# feather-v2_0.net
KiCad netlist of a schematic drawn in EAGLE
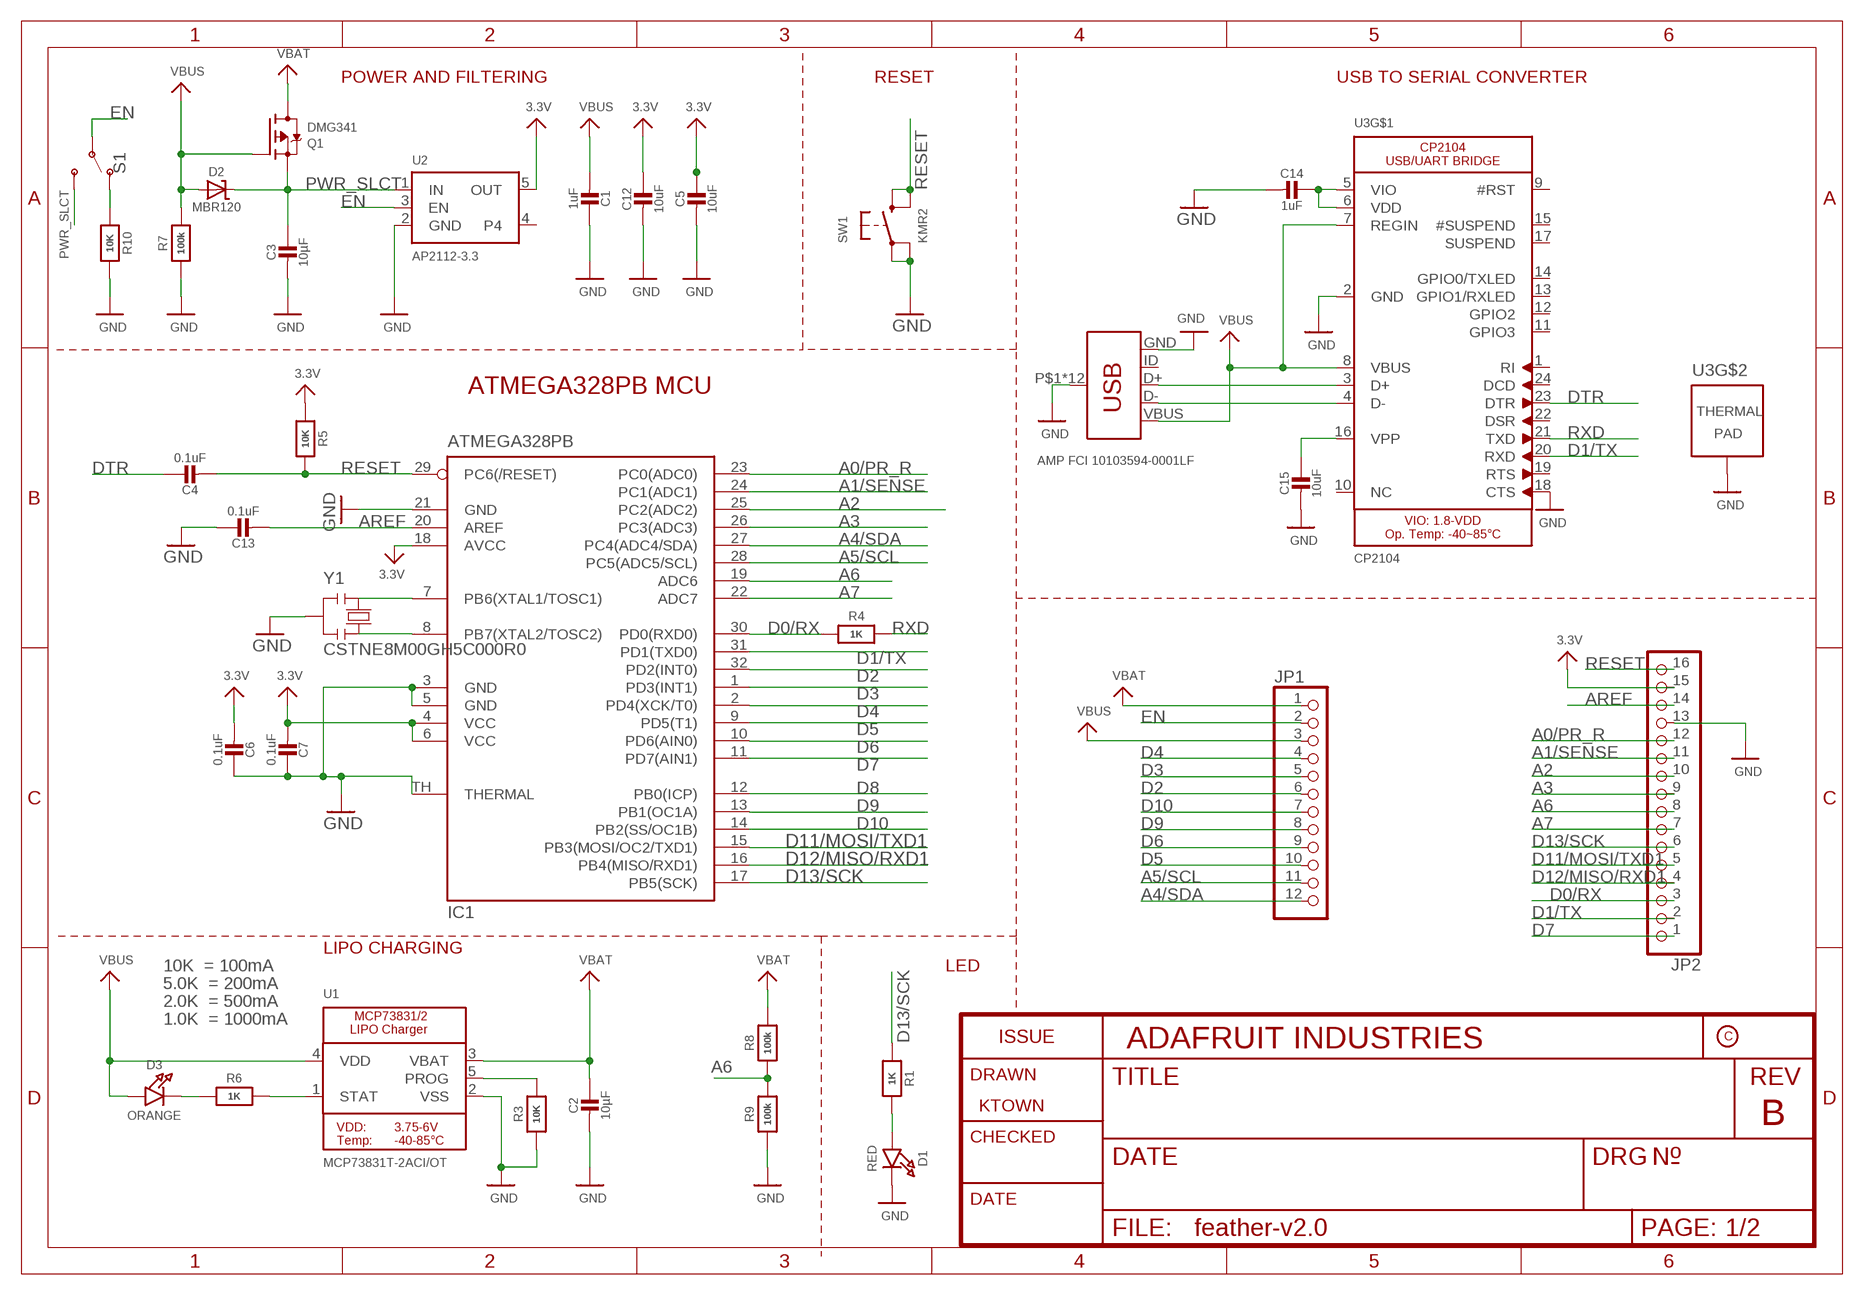
[diagram p0: schematic, sheet 1]
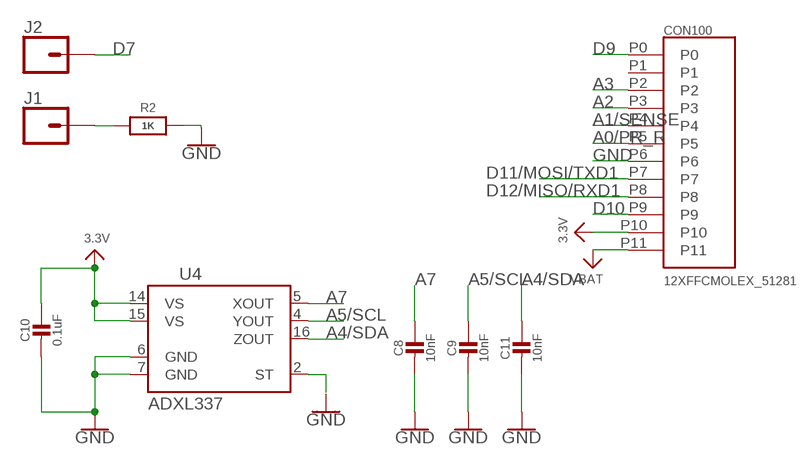
[diagram p1: schematic, sheet 2]

(export (version "E")
  (design (tool "Eeschema 10.0.6"))
  (components
    (comp (ref "C8")
      (value "10nF")
      (footprint "eagle-import:_0603MP")
      (libsource (lib "eagle-import") (part "CAP_CERAMIC_0603MP"))
    )
    (comp (ref "C9")
      (value "10nF")
      (footprint "eagle-import:_0603MP")
      (libsource (lib "eagle-import") (part "CAP_CERAMIC_0603MP"))
    )
    (comp (ref "C10")
      (value "0.1uF")
      (footprint "eagle-import:_0603MP")
      (libsource (lib "eagle-import") (part "CAP_CERAMIC_0603MP"))
    )
    (comp (ref "C11")
      (value "10nF")
      (footprint "eagle-import:_0603MP")
      (libsource (lib "eagle-import") (part "CAP_CERAMIC_0603MP"))
    )
    (comp (ref "CON100")
      (value "12XFFCMOLEX_51281")
      (footprint "eagle-import:MOLEX_51281-1294")
      (libsource (lib "eagle-import") (part "12XFFCMOLEX_51281"))
    )
    (comp (ref "J1")
      (value "CONN_01PTH_NO_SILK_YES_STOP")
      (footprint "eagle-import:1X01_NO_SILK")
      (libsource (lib "eagle-import") (part "CONN_01PTH_NO_SILK_YES_STOP"))
    )
    (comp (ref "J2")
      (value "CONN_01PTH_NO_SILK_YES_STOP")
      (footprint "eagle-import:1X01_NO_SILK")
      (libsource (lib "eagle-import") (part "CONN_01PTH_NO_SILK_YES_STOP"))
    )
    (comp (ref "R2")
      (value "1K")
      (footprint "eagle-import:_0603MP")
      (libsource (lib "eagle-import") (part "RESISTOR_0603MP"))
    )
    (comp (ref "U4")
      (value "ADXL337")
      (footprint "eagle-import:LFCSP_LQ-16")
      (libsource (lib "eagle-import") (part "ADXL337"))
    )
    (comp (ref "C1")
      (value "1uF")
      (footprint "eagle-import:_0603MP")
      (libsource (lib "eagle-import") (part "CAP_CERAMIC_0603MP"))
    )
    (comp (ref "C2")
      (value "10µF")
      (footprint "eagle-import:_0603MP")
      (libsource (lib "eagle-import") (part "CAP_CERAMIC_0603MP"))
    )
    (comp (ref "C3")
      (value "10µF")
      (footprint "eagle-import:_0603MP")
      (libsource (lib "eagle-import") (part "CAP_CERAMIC_0603MP"))
    )
    (comp (ref "C4")
      (value "0.1uF")
      (footprint "eagle-import:_0603MP")
      (libsource (lib "eagle-import") (part "CAP_CERAMIC_0603MP"))
    )
    (comp (ref "C5")
      (value "10uF")
      (footprint "eagle-import:_0603MP")
      (libsource (lib "eagle-import") (part "CAP_CERAMIC_0603MP"))
    )
    (comp (ref "C6")
      (value "0.1uF")
      (footprint "eagle-import:_0603MP")
      (libsource (lib "eagle-import") (part "CAP_CERAMIC_0603MP"))
    )
    (comp (ref "C7")
      (value "0.1uF")
      (footprint "eagle-import:_0603MP")
      (libsource (lib "eagle-import") (part "CAP_CERAMIC_0603MP"))
    )
    (comp (ref "C12")
      (value "10uF")
      (footprint "eagle-import:_0603MP")
      (libsource (lib "eagle-import") (part "CAP_CERAMIC_0603MP"))
    )
    (comp (ref "C13")
      (value "0.1uF")
      (footprint "eagle-import:_0603MP")
      (libsource (lib "eagle-import") (part "CAP_CERAMIC_0603MP"))
    )
    (comp (ref "C14")
      (value "1uF")
      (footprint "eagle-import:_0603MP")
      (libsource (lib "eagle-import") (part "CAP_CERAMIC_0603MP"))
    )
    (comp (ref "C15")
      (value "10uF")
      (footprint "eagle-import:_0603MP")
      (libsource (lib "eagle-import") (part "CAP_CERAMIC_0603MP"))
    )
    (comp (ref "D1")
      (value "RED")
      (footprint "eagle-import:CHIPLED_0603_NOOUTLINE")
      (libsource (lib "eagle-import") (part "LED0603_NOOUTLINE"))
    )
    (comp (ref "D2")
      (value "MBR120")
      (footprint "eagle-import:SOD-323")
      (libsource (lib "eagle-import") (part "DIODE-SCHOTTKYSOD-323"))
    )
    (comp (ref "D3")
      (value "ORANGE")
      (footprint "eagle-import:CHIPLED_0603_NOOUTLINE")
      (libsource (lib "eagle-import") (part "LED0603_NOOUTLINE"))
    )
    (comp (ref "IC1")
      (value "ATMEGA328PB")
      (footprint "eagle-import:MLF32-TH")
      (fields (field (name "MPN") "ATMEGA88PA-MU"))
      (libsource (lib "eagle-import") (part "MEGA8-MI"))
    )
    (comp (ref "JP1")
      (value "HEADER-1X12")
      (footprint "eagle-import:1X12_ROUND")
      (libsource (lib "eagle-import") (part "HEADER-1X12"))
    )
    (comp (ref "JP2")
      (value "HEADER-1X16ROUND")
      (footprint "eagle-import:1X16_ROUND")
      (libsource (lib "eagle-import") (part "HEADER-1X16ROUND"))
    )
    (comp (ref "Q1")
      (value "DMG341")
      (footprint "eagle-import:SOT23-R")
      (libsource (lib "eagle-import") (part "MOSFET-P"))
    )
    (comp (ref "R1")
      (value "1K")
      (footprint "eagle-import:_0603MP")
      (libsource (lib "eagle-import") (part "RESISTOR_0603MP"))
    )
    (comp (ref "R3")
      (value "10K")
      (footprint "eagle-import:_0603MP")
      (libsource (lib "eagle-import") (part "RESISTOR_0603MP"))
    )
    (comp (ref "R4")
      (value "1K")
      (footprint "eagle-import:_0603MP")
      (libsource (lib "eagle-import") (part "RESISTOR_0603MP"))
    )
    (comp (ref "R5")
      (value "10K")
      (footprint "eagle-import:_0603MP")
      (libsource (lib "eagle-import") (part "RESISTOR_0603MP"))
    )
    (comp (ref "R6")
      (value "1K")
      (footprint "eagle-import:_0603MP")
      (libsource (lib "eagle-import") (part "RESISTOR_0603MP"))
    )
    (comp (ref "R7")
      (value "100k")
      (footprint "eagle-import:_0603MP")
      (libsource (lib "eagle-import") (part "RESISTOR_0603MP"))
    )
    (comp (ref "R8")
      (value "100k")
      (footprint "eagle-import:_0603MP")
      (libsource (lib "eagle-import") (part "RESISTOR_0603MP"))
    )
    (comp (ref "R9")
      (value "100k")
      (footprint "eagle-import:_0603MP")
      (libsource (lib "eagle-import") (part "RESISTOR_0603MP"))
    )
    (comp (ref "R10")
      (value "10K")
      (footprint "eagle-import:_0603MP")
      (libsource (lib "eagle-import") (part "RESISTOR_0603MP"))
    )
    (comp (ref "S1")
      (value "SWITCH-SPDT-SMD-RIGHT-ANGLE")
      (footprint "eagle-import:SWITCH_SPST_SMD_A")
      (libsource (lib "eagle-import") (part "SWITCH-SPDT-SMD-RIGHT-ANGLE"))
    )
    (comp (ref "SW1")
      (value "KMR2")
      (footprint "eagle-import:BTN_KMR2_4.6X2.8")
      (libsource (lib "eagle-import") (part "SWITCH_TACT_SMT4.6X2.8"))
    )
    (comp (ref "U1")
      (value "MCP73831T-2ACI/OT")
      (footprint "eagle-import:SOT23-5")
      (libsource (lib "eagle-import") (part "MCP73831/2"))
    )
    (comp (ref "U2")
      (value "AP2112-3.3")
      (footprint "eagle-import:SOT23-5")
      (libsource (lib "eagle-import") (part "VREG_SOT23-5"))
    )
    (comp (ref "U3")
      (value "CP2104")
      (footprint "eagle-import:QFN24_4MM_SMSC")
      (libsource (lib "eagle-import") (part "CP2104"))
    )
    (comp (ref "X1")
      (value "AMP FCI 10103594-0001LF")
      (footprint "eagle-import:USB-MICROB-PTH")
      (libsource (lib "eagle-import") (part "USB_MICRO-B_HALF_PTH"))
    )
    (comp (ref "Y1")
      (value "CSTNE8M00GH5C000R0")
      (footprint "eagle-import:RESONATOR")
      (libsource (lib "eagle-import") (part "RESONATORMU"))
    )
  )
  (nets
    (net (code "1") (name "3.3V") (class "Default")
      (node (ref "C10") (pin "1") (pinfunction "1_1") (pintype "passive"))
      (node (ref "C12") (pin "1") (pinfunction "1_1") (pintype "passive"))
      (node (ref "C5") (pin "1") (pinfunction "1_1") (pintype "passive"))
      (node (ref "C6") (pin "2") (pinfunction "2_2") (pintype "passive"))
      (node (ref "C7") (pin "2") (pinfunction "2_2") (pintype "passive"))
      (node (ref "CON100") (pin "P10") (pinfunction "P10_P10") (pintype "bidirectional"))
      (node (ref "IC1") (pin "18") (pinfunction "AVCC_18") (pintype "power_in"))
      (node (ref "IC1") (pin "4") (pinfunction "VCC_4") (pintype "power_in"))
      (node (ref "IC1") (pin "6") (pinfunction "VCC_6") (pintype "power_in"))
      (node (ref "JP2") (pin "15") (pinfunction "15_15") (pintype "passive"))
      (node (ref "R5") (pin "2") (pinfunction "2_2") (pintype "passive"))
      (node (ref "U2") (pin "5") (pinfunction "OUT_5") (pintype "power_in"))
      (node (ref "U4") (pin "14") (pinfunction "VS_14") (pintype "bidirectional"))
      (node (ref "U4") (pin "15") (pinfunction "VS_15") (pintype "bidirectional"))
    )
    (net (code "2") (name "A0{slash}PR_R") (class "Default")
      (node (ref "CON100") (pin "P5") (pinfunction "P5_P5") (pintype "bidirectional"))
      (node (ref "IC1") (pin "23") (pinfunction "PC0(ADC0)_23") (pintype "bidirectional"))
      (node (ref "JP2") (pin "12") (pinfunction "12_12") (pintype "passive"))
    )
    (net (code "3") (name "A1{slash}SENSE") (class "Default")
      (node (ref "CON100") (pin "P4") (pinfunction "P4_P4") (pintype "bidirectional"))
      (node (ref "IC1") (pin "24") (pinfunction "PC1(ADC1)_24") (pintype "bidirectional"))
      (node (ref "JP2") (pin "11") (pinfunction "11_11") (pintype "passive"))
    )
    (net (code "4") (name "A2") (class "Default")
      (node (ref "CON100") (pin "P3") (pinfunction "P3_P3") (pintype "bidirectional"))
      (node (ref "IC1") (pin "25") (pinfunction "PC2(ADC2)_25") (pintype "bidirectional"))
      (node (ref "JP2") (pin "10") (pinfunction "10_10") (pintype "passive"))
    )
    (net (code "5") (name "A3") (class "Default")
      (node (ref "CON100") (pin "P2") (pinfunction "P2_P2") (pintype "bidirectional"))
      (node (ref "IC1") (pin "26") (pinfunction "PC3(ADC3)_26") (pintype "bidirectional"))
      (node (ref "JP2") (pin "9") (pinfunction "9_9") (pintype "passive"))
    )
    (net (code "6") (name "A4{slash}SDA") (class "Default")
      (node (ref "C11") (pin "1") (pinfunction "1_1") (pintype "passive"))
      (node (ref "IC1") (pin "27") (pinfunction "PC4(ADC4/SDA)_27") (pintype "bidirectional"))
      (node (ref "JP1") (pin "12") (pinfunction "12_12") (pintype "passive"))
      (node (ref "U4") (pin "16") (pinfunction "ZOUT_16") (pintype "bidirectional"))
    )
    (net (code "7") (name "A5{slash}SCL") (class "Default")
      (node (ref "C9") (pin "1") (pinfunction "1_1") (pintype "passive"))
      (node (ref "IC1") (pin "28") (pinfunction "PC5(ADC5/SCL)_28") (pintype "bidirectional"))
      (node (ref "JP1") (pin "11") (pinfunction "11_11") (pintype "passive"))
      (node (ref "U4") (pin "4") (pinfunction "YOUT_4") (pintype "bidirectional"))
    )
    (net (code "8") (name "A6") (class "Default")
      (node (ref "IC1") (pin "19") (pinfunction "ADC6_19") (pintype "bidirectional"))
      (node (ref "JP2") (pin "8") (pinfunction "8_8") (pintype "passive"))
      (node (ref "R8") (pin "1") (pinfunction "1_1") (pintype "passive"))
      (node (ref "R9") (pin "2") (pinfunction "2_2") (pintype "passive"))
    )
    (net (code "9") (name "A7") (class "Default")
      (node (ref "C8") (pin "1") (pinfunction "1_1") (pintype "passive"))
      (node (ref "IC1") (pin "22") (pinfunction "ADC7_22") (pintype "bidirectional"))
      (node (ref "JP2") (pin "7") (pinfunction "7_7") (pintype "passive"))
      (node (ref "U4") (pin "5") (pinfunction "XOUT_5") (pintype "bidirectional"))
    )
    (net (code "10") (name "AREF") (class "Default")
      (node (ref "C13") (pin "2") (pinfunction "2_2") (pintype "passive"))
      (node (ref "IC1") (pin "20") (pinfunction "AREF_20") (pintype "passive"))
      (node (ref "JP2") (pin "14") (pinfunction "14_14") (pintype "passive"))
    )
    (net (code "11") (name "D0{slash}RX") (class "Default")
      (node (ref "IC1") (pin "30") (pinfunction "PD0(RXD0)_30") (pintype "bidirectional"))
      (node (ref "JP2") (pin "3") (pinfunction "3_3") (pintype "passive"))
      (node (ref "R4") (pin "1") (pinfunction "1_1") (pintype "passive"))
    )
    (net (code "12") (name "D1{slash}TX") (class "Default")
      (node (ref "IC1") (pin "31") (pinfunction "PD1(TXD0)_31") (pintype "bidirectional"))
      (node (ref "JP2") (pin "2") (pinfunction "2_2") (pintype "passive"))
      (node (ref "U3") (pin "20") (pinfunction "RXD_20") (pintype "input"))
    )
    (net (code "13") (name "D2") (class "Default")
      (node (ref "IC1") (pin "32") (pinfunction "PD2(INT0)_32") (pintype "bidirectional"))
      (node (ref "JP1") (pin "6") (pinfunction "6_6") (pintype "passive"))
    )
    (net (code "14") (name "D3") (class "Default")
      (node (ref "IC1") (pin "1") (pinfunction "PD3(INT1)_1") (pintype "bidirectional"))
      (node (ref "JP1") (pin "5") (pinfunction "5_5") (pintype "passive"))
    )
    (net (code "15") (name "D4") (class "Default")
      (node (ref "IC1") (pin "2") (pinfunction "PD4(XCK/T0)_2") (pintype "bidirectional"))
      (node (ref "JP1") (pin "4") (pinfunction "4_4") (pintype "passive"))
    )
    (net (code "16") (name "D5") (class "Default")
      (node (ref "IC1") (pin "9") (pinfunction "PD5(T1)_9") (pintype "bidirectional"))
      (node (ref "JP1") (pin "10") (pinfunction "10_10") (pintype "passive"))
    )
    (net (code "17") (name "D6") (class "Default")
      (node (ref "IC1") (pin "10") (pinfunction "PD6(AIN0)_10") (pintype "bidirectional"))
      (node (ref "JP1") (pin "9") (pinfunction "9_9") (pintype "passive"))
    )
    (net (code "18") (name "D7") (class "Default")
      (node (ref "IC1") (pin "11") (pinfunction "PD7(AIN1)_11") (pintype "bidirectional"))
      (node (ref "J2") (pin "1") (pinfunction "1_1") (pintype "passive"))
      (node (ref "JP2") (pin "1") (pinfunction "1_1") (pintype "passive"))
    )
    (net (code "19") (name "D8") (class "Default")
      (node (ref "IC1") (pin "12") (pinfunction "PB0(ICP)_12") (pintype "bidirectional"))
    )
    (net (code "20") (name "D9") (class "Default")
      (node (ref "CON100") (pin "P0") (pinfunction "P0_P0") (pintype "bidirectional"))
      (node (ref "IC1") (pin "13") (pinfunction "PB1(OC1A)_13") (pintype "bidirectional"))
      (node (ref "JP1") (pin "8") (pinfunction "8_8") (pintype "passive"))
    )
    (net (code "21") (name "D10") (class "Default")
      (node (ref "CON100") (pin "P9") (pinfunction "P9_P9") (pintype "bidirectional"))
      (node (ref "IC1") (pin "14") (pinfunction "PB2(SS/OC1B)_14") (pintype "bidirectional"))
      (node (ref "JP1") (pin "7") (pinfunction "7_7") (pintype "passive"))
    )
    (net (code "22") (name "D11{slash}MOSI{slash}TXD1") (class "Default")
      (node (ref "CON100") (pin "P7") (pinfunction "P7_P7") (pintype "bidirectional"))
      (node (ref "IC1") (pin "15") (pinfunction "PB3(MOSI/OC2/TXD1)_15") (pintype "bidirectional"))
      (node (ref "JP2") (pin "5") (pinfunction "5_5") (pintype "passive"))
    )
    (net (code "23") (name "D12{slash}MISO{slash}RXD1") (class "Default")
      (node (ref "CON100") (pin "P8") (pinfunction "P8_P8") (pintype "bidirectional"))
      (node (ref "IC1") (pin "16") (pinfunction "PB4(MISO/RXD1)_16") (pintype "bidirectional"))
      (node (ref "JP2") (pin "4") (pinfunction "4_4") (pintype "passive"))
    )
    (net (code "24") (name "D13{slash}SCK") (class "Default")
      (node (ref "IC1") (pin "17") (pinfunction "PB5(SCK)_17") (pintype "bidirectional"))
      (node (ref "JP2") (pin "6") (pinfunction "6_6") (pintype "passive"))
      (node (ref "R1") (pin "1") (pinfunction "1_1") (pintype "passive"))
    )
    (net (code "25") (name "DTR") (class "Default")
      (node (ref "C4") (pin "1") (pinfunction "1_1") (pintype "passive"))
      (node (ref "U3") (pin "23") (pinfunction "DTR_23") (pintype "output"))
    )
    (net (code "26") (name "EN") (class "Default")
      (node (ref "JP1") (pin "2") (pinfunction "2_2") (pintype "passive"))
      (node (ref "S1") (pin "2") (pinfunction "P_2") (pintype "passive"))
      (node (ref "U2") (pin "3") (pinfunction "EN_3") (pintype "input"))
    )
    (net (code "27") (name "GND") (class "Default")
      (node (ref "C1") (pin "1") (pinfunction "1_1") (pintype "passive"))
      (node (ref "C10") (pin "2") (pinfunction "2_2") (pintype "passive"))
      (node (ref "C11") (pin "2") (pinfunction "2_2") (pintype "passive"))
      (node (ref "C12") (pin "2") (pinfunction "2_2") (pintype "passive"))
      (node (ref "C13") (pin "1") (pinfunction "1_1") (pintype "passive"))
      (node (ref "C14") (pin "2") (pinfunction "2_2") (pintype "passive"))
      (node (ref "C15") (pin "2") (pinfunction "2_2") (pintype "passive"))
      (node (ref "C2") (pin "2") (pinfunction "2_2") (pintype "passive"))
      (node (ref "C3") (pin "2") (pinfunction "2_2") (pintype "passive"))
      (node (ref "C5") (pin "2") (pinfunction "2_2") (pintype "passive"))
      (node (ref "C6") (pin "1") (pinfunction "1_1") (pintype "passive"))
      (node (ref "C7") (pin "1") (pinfunction "1_1") (pintype "passive"))
      (node (ref "C8") (pin "2") (pinfunction "2_2") (pintype "passive"))
      (node (ref "C9") (pin "2") (pinfunction "2_2") (pintype "passive"))
      (node (ref "CON100") (pin "P6") (pinfunction "P6_P6") (pintype "bidirectional"))
      (node (ref "D1") (pin "C") (pinfunction "C_C") (pintype "passive"))
      (node (ref "IC1") (pin "21") (pinfunction "GND_21") (pintype "power_in"))
      (node (ref "IC1") (pin "3") (pinfunction "GND_3") (pintype "power_in"))
      (node (ref "IC1") (pin "5") (pinfunction "GND_5") (pintype "power_in"))
      (node (ref "IC1") (pin "TH") (pinfunction "THERMAL_TH") (pintype "passive"))
      (node (ref "JP2") (pin "13") (pinfunction "13_13") (pintype "passive"))
      (node (ref "R10") (pin "1") (pinfunction "1_1") (pintype "passive"))
      (node (ref "R2") (pin "2") (pinfunction "2_2") (pintype "passive"))
      (node (ref "R3") (pin "1") (pinfunction "1_1") (pintype "passive"))
      (node (ref "R7") (pin "1") (pinfunction "1_1") (pintype "passive"))
      (node (ref "R9") (pin "1") (pinfunction "1_1") (pintype "passive"))
      (node (ref "SW1") (pin "A") (pinfunction "P_A") (pintype "passive"))
      (node (ref "SW1") (pin "A'") (pinfunction "P1_A'") (pintype "passive"))
      (node (ref "U1") (pin "2") (pinfunction "VSS_2") (pintype "power_in"))
      (node (ref "U2") (pin "2") (pinfunction "GND_2") (pintype "power_in"))
      (node (ref "U3") (pin "18") (pinfunction "CTS_18") (pintype "input"))
      (node (ref "U3") (pin "2") (pinfunction "GND_2") (pintype "power_in"))
      (node (ref "U3") (pin "THERM") (pinfunction "TP_THERM") (pintype "power_in"))
      (node (ref "U4") (pin "6") (pinfunction "GND_6") (pintype "bidirectional"))
      (node (ref "U4") (pin "7") (pinfunction "GND_7") (pintype "bidirectional"))
      (node (ref "X1") (pin "GND") (pinfunction "GND_GND") (pintype "power_in"))
      (node (ref "X1") (pin "P$1") (pinfunction "SHIELD_P$1") (pintype "bidirectional"))
      (node (ref "X1") (pin "P$10") (pinfunction "SHIELD_P$10") (pintype "bidirectional"))
      (node (ref "X1") (pin "P$12") (pinfunction "SHIELD_P$12") (pintype "bidirectional"))
      (node (ref "X1") (pin "P$2") (pinfunction "SHIELD_P$2") (pintype "bidirectional"))
      (node (ref "X1") (pin "P$3") (pinfunction "SHIELD_P$3") (pintype "bidirectional"))
      (node (ref "X1") (pin "P$4") (pinfunction "SHIELD_P$4") (pintype "bidirectional"))
      (node (ref "X1") (pin "P$6") (pinfunction "SHIELD_P$6") (pintype "bidirectional"))
      (node (ref "X1") (pin "P$8") (pinfunction "SHIELD_P$8") (pintype "bidirectional"))
      (node (ref "X1") (pin "SHEILD2") (pinfunction "SHIELD_SHEILD2") (pintype "bidirectional"))
      (node (ref "X1") (pin "SHIELD") (pinfunction "SHIELD_SHIELD") (pintype "bidirectional"))
      (node (ref "X1") (pin "SHIELD3") (pinfunction "SHIELD_SHIELD3") (pintype "bidirectional"))
      (node (ref "X1") (pin "SHIELD4") (pinfunction "SHIELD_SHIELD4") (pintype "bidirectional"))
      (node (ref "Y1") (pin "2") (pinfunction "2_2") (pintype "passive"))
    )
    (net (code "28") (name "Net-(D1-PadA)") (class "Default")
      (node (ref "D1") (pin "A") (pinfunction "A_A") (pintype "passive"))
      (node (ref "R1") (pin "2") (pinfunction "2_2") (pintype "passive"))
    )
    (net (code "29") (name "Net-(D3-PadC)") (class "Default")
      (node (ref "D3") (pin "C") (pinfunction "C_C") (pintype "passive"))
      (node (ref "R6") (pin "1") (pinfunction "1_1") (pintype "passive"))
    )
    (net (code "30") (name "Net-(IC1-PB6(XTAL1{slash}TOSC1))") (class "Default")
      (node (ref "IC1") (pin "7") (pinfunction "PB6(XTAL1/TOSC1)_7") (pintype "bidirectional"))
      (node (ref "Y1") (pin "1") (pinfunction "1_1") (pintype "passive"))
    )
    (net (code "31") (name "Net-(IC1-PB7(XTAL2{slash}TOSC2))") (class "Default")
      (node (ref "IC1") (pin "8") (pinfunction "PB7(XTAL2/TOSC2)_8") (pintype "bidirectional"))
      (node (ref "Y1") (pin "3") (pinfunction "3_3") (pintype "passive"))
    )
    (net (code "32") (name "Net-(J1-Pad1)") (class "Default")
      (node (ref "J1") (pin "1") (pinfunction "1_1") (pintype "passive"))
      (node (ref "R2") (pin "1") (pinfunction "1_1") (pintype "passive"))
    )
    (net (code "33") (name "Net-(S1-O)") (class "Default")
      (node (ref "R10") (pin "2") (pinfunction "2_2") (pintype "passive"))
      (node (ref "S1") (pin "1") (pinfunction "O_1") (pintype "passive"))
    )
    (net (code "34") (name "Net-(U1-PROG)") (class "Default")
      (node (ref "R3") (pin "2") (pinfunction "2_2") (pintype "passive"))
      (node (ref "U1") (pin "5") (pinfunction "PROG_5") (pintype "input"))
    )
    (net (code "35") (name "Net-(U1-STAT)") (class "Default")
      (node (ref "R6") (pin "2") (pinfunction "2_2") (pintype "passive"))
      (node (ref "U1") (pin "1") (pinfunction "STAT_1") (pintype "output"))
    )
    (net (code "36") (name "Net-(U3A-D+)") (class "Default")
      (node (ref "U3") (pin "3") (pinfunction "D+_3") (pintype "bidirectional"))
      (node (ref "X1") (pin "D+") (pinfunction "D+_D+") (pintype "bidirectional"))
    )
    (net (code "37") (name "Net-(U3A-D-)") (class "Default")
      (node (ref "U3") (pin "4") (pinfunction "D-_4") (pintype "bidirectional"))
      (node (ref "X1") (pin "D-") (pinfunction "D-_D-") (pintype "bidirectional"))
    )
    (net (code "38") (name "Net-(U3A-VDD)") (class "Default")
      (node (ref "C14") (pin "1") (pinfunction "1_1") (pintype "passive"))
      (node (ref "U3") (pin "5") (pinfunction "VIO_5") (pintype "power_in"))
      (node (ref "U3") (pin "6") (pinfunction "VDD_6") (pintype "power_in"))
    )
    (net (code "39") (name "Net-(U3A-VPP)") (class "Default")
      (node (ref "C15") (pin "1") (pinfunction "1_1") (pintype "passive"))
      (node (ref "U3") (pin "16") (pinfunction "VPP_16") (pintype "bidirectional"))
    )
    (net (code "40") (name "PWR_SLCT") (class "Default")
      (node (ref "C3") (pin "1") (pinfunction "1_1") (pintype "passive"))
      (node (ref "D2") (pin "C") (pinfunction "C_C") (pintype "passive"))
      (node (ref "Q1") (pin "2") (pinfunction "S_2") (pintype "passive"))
      (node (ref "S1") (pin "3") (pinfunction "S_3") (pintype "passive"))
      (node (ref "U2") (pin "1") (pinfunction "IN_1") (pintype "power_in"))
    )
    (net (code "41") (name "RESET") (class "Default")
      (node (ref "C4") (pin "2") (pinfunction "2_2") (pintype "passive"))
      (node (ref "IC1") (pin "29") (pinfunction "PC6(/RESET)_29") (pintype "bidirectional"))
      (node (ref "JP2") (pin "16") (pinfunction "16_16") (pintype "passive"))
      (node (ref "R5") (pin "1") (pinfunction "1_1") (pintype "passive"))
      (node (ref "SW1") (pin "B") (pinfunction "S_B") (pintype "passive"))
      (node (ref "SW1") (pin "B'") (pinfunction "S1_B'") (pintype "passive"))
    )
    (net (code "42") (name "RXD") (class "Default")
      (node (ref "R4") (pin "2") (pinfunction "2_2") (pintype "passive"))
      (node (ref "U3") (pin "21") (pinfunction "TXD_21") (pintype "output"))
    )
    (net (code "43") (name "VBAT") (class "Default")
      (node (ref "C2") (pin "1") (pinfunction "1_1") (pintype "passive"))
      (node (ref "CON100") (pin "P11") (pinfunction "P11_P11") (pintype "bidirectional"))
      (node (ref "JP1") (pin "1") (pinfunction "1_1") (pintype "passive"))
      (node (ref "Q1") (pin "3") (pinfunction "D_3") (pintype "passive"))
      (node (ref "R8") (pin "2") (pinfunction "2_2") (pintype "passive"))
      (node (ref "U1") (pin "3") (pinfunction "VBAT_3") (pintype "power_in"))
    )
    (net (code "44") (name "VBUS") (class "Default")
      (node (ref "C1") (pin "2") (pinfunction "2_2") (pintype "passive"))
      (node (ref "D2") (pin "A") (pinfunction "A_A") (pintype "passive"))
      (node (ref "D3") (pin "A") (pinfunction "A_A") (pintype "passive"))
      (node (ref "JP1") (pin "3") (pinfunction "3_3") (pintype "passive"))
      (node (ref "Q1") (pin "1") (pinfunction "G_1") (pintype "passive"))
      (node (ref "R7") (pin "2") (pinfunction "2_2") (pintype "passive"))
      (node (ref "U1") (pin "4") (pinfunction "VDD_4") (pintype "power_in"))
      (node (ref "U3") (pin "7") (pinfunction "REGIN_7") (pintype "power_in"))
      (node (ref "U3") (pin "8") (pinfunction "VBUS_8") (pintype "power_in"))
      (node (ref "X1") (pin "VBUS") (pinfunction "VBUS_VBUS") (pintype "power_in"))
    )
    (net (code "45") (name "unconnected-(CON100-PadP1)") (class "Default")
      (node (ref "CON100") (pin "P1") (pinfunction "P1_P1") (pintype "bidirectional"))
    )
    (net (code "46") (name "unconnected-(U2-P4-Pad4)") (class "Default")
      (node (ref "U2") (pin "4") (pinfunction "P4_4") (pintype "bidirectional"))
    )
    (net (code "47") (name "unconnected-(U3A-#RST-Pad9)") (class "Default")
      (node (ref "U3") (pin "9") (pinfunction "#RST_9") (pintype "bidirectional"))
    )
    (net (code "48") (name "unconnected-(U3A-#SUSPEND-Pad15)") (class "Default")
      (node (ref "U3") (pin "15") (pinfunction "#SUSPEND_15") (pintype "output"))
    )
    (net (code "49") (name "unconnected-(U3A-DCD-Pad24)") (class "Default")
      (node (ref "U3") (pin "24") (pinfunction "DCD_24") (pintype "input"))
    )
    (net (code "50") (name "unconnected-(U3A-DSR-Pad22)") (class "Default")
      (node (ref "U3") (pin "22") (pinfunction "DSR_22") (pintype "input"))
    )
    (net (code "51") (name "unconnected-(U3A-GPIO0{slash}TXLED-Pad14)") (class "Default")
      (node (ref "U3") (pin "14") (pinfunction "GPIO0/TXLED_14") (pintype "bidirectional"))
    )
    (net (code "52") (name "unconnected-(U3A-GPIO1{slash}RXLED-Pad13)") (class "Default")
      (node (ref "U3") (pin "13") (pinfunction "GPIO1/RXLED_13") (pintype "bidirectional"))
    )
    (net (code "53") (name "unconnected-(U3A-GPIO2-Pad12)") (class "Default")
      (node (ref "U3") (pin "12") (pinfunction "GPIO2_12") (pintype "bidirectional"))
    )
    (net (code "54") (name "unconnected-(U3A-GPIO3-Pad11)") (class "Default")
      (node (ref "U3") (pin "11") (pinfunction "GPIO3_11") (pintype "bidirectional"))
    )
    (net (code "55") (name "unconnected-(U3A-NC-Pad10)") (class "Default")
      (node (ref "U3") (pin "10") (pinfunction "NC_10") (pintype "no_connect"))
    )
    (net (code "56") (name "unconnected-(U3A-RI-Pad1)") (class "Default")
      (node (ref "U3") (pin "1") (pinfunction "RI_1") (pintype "input"))
    )
    (net (code "57") (name "unconnected-(U3A-RTS-Pad19)") (class "Default")
      (node (ref "U3") (pin "19") (pinfunction "RTS_19") (pintype "output"))
    )
    (net (code "58") (name "unconnected-(U3A-SUSPEND-Pad17)") (class "Default")
      (node (ref "U3") (pin "17") (pinfunction "SUSPEND_17") (pintype "output"))
    )
    (net (code "59") (name "unconnected-(U4-ST-Pad2)") (class "Default")
      (node (ref "U4") (pin "2") (pinfunction "ST_2") (pintype "bidirectional"))
    )
    (net (code "60") (name "unconnected-(X1-PadID)") (class "Default")
      (node (ref "X1") (pin "ID") (pinfunction "ID_ID") (pintype "bidirectional"))
    )
  )
)
